# Sheet1.net
KiCad netlist of a schematic drawn in Altium Designer
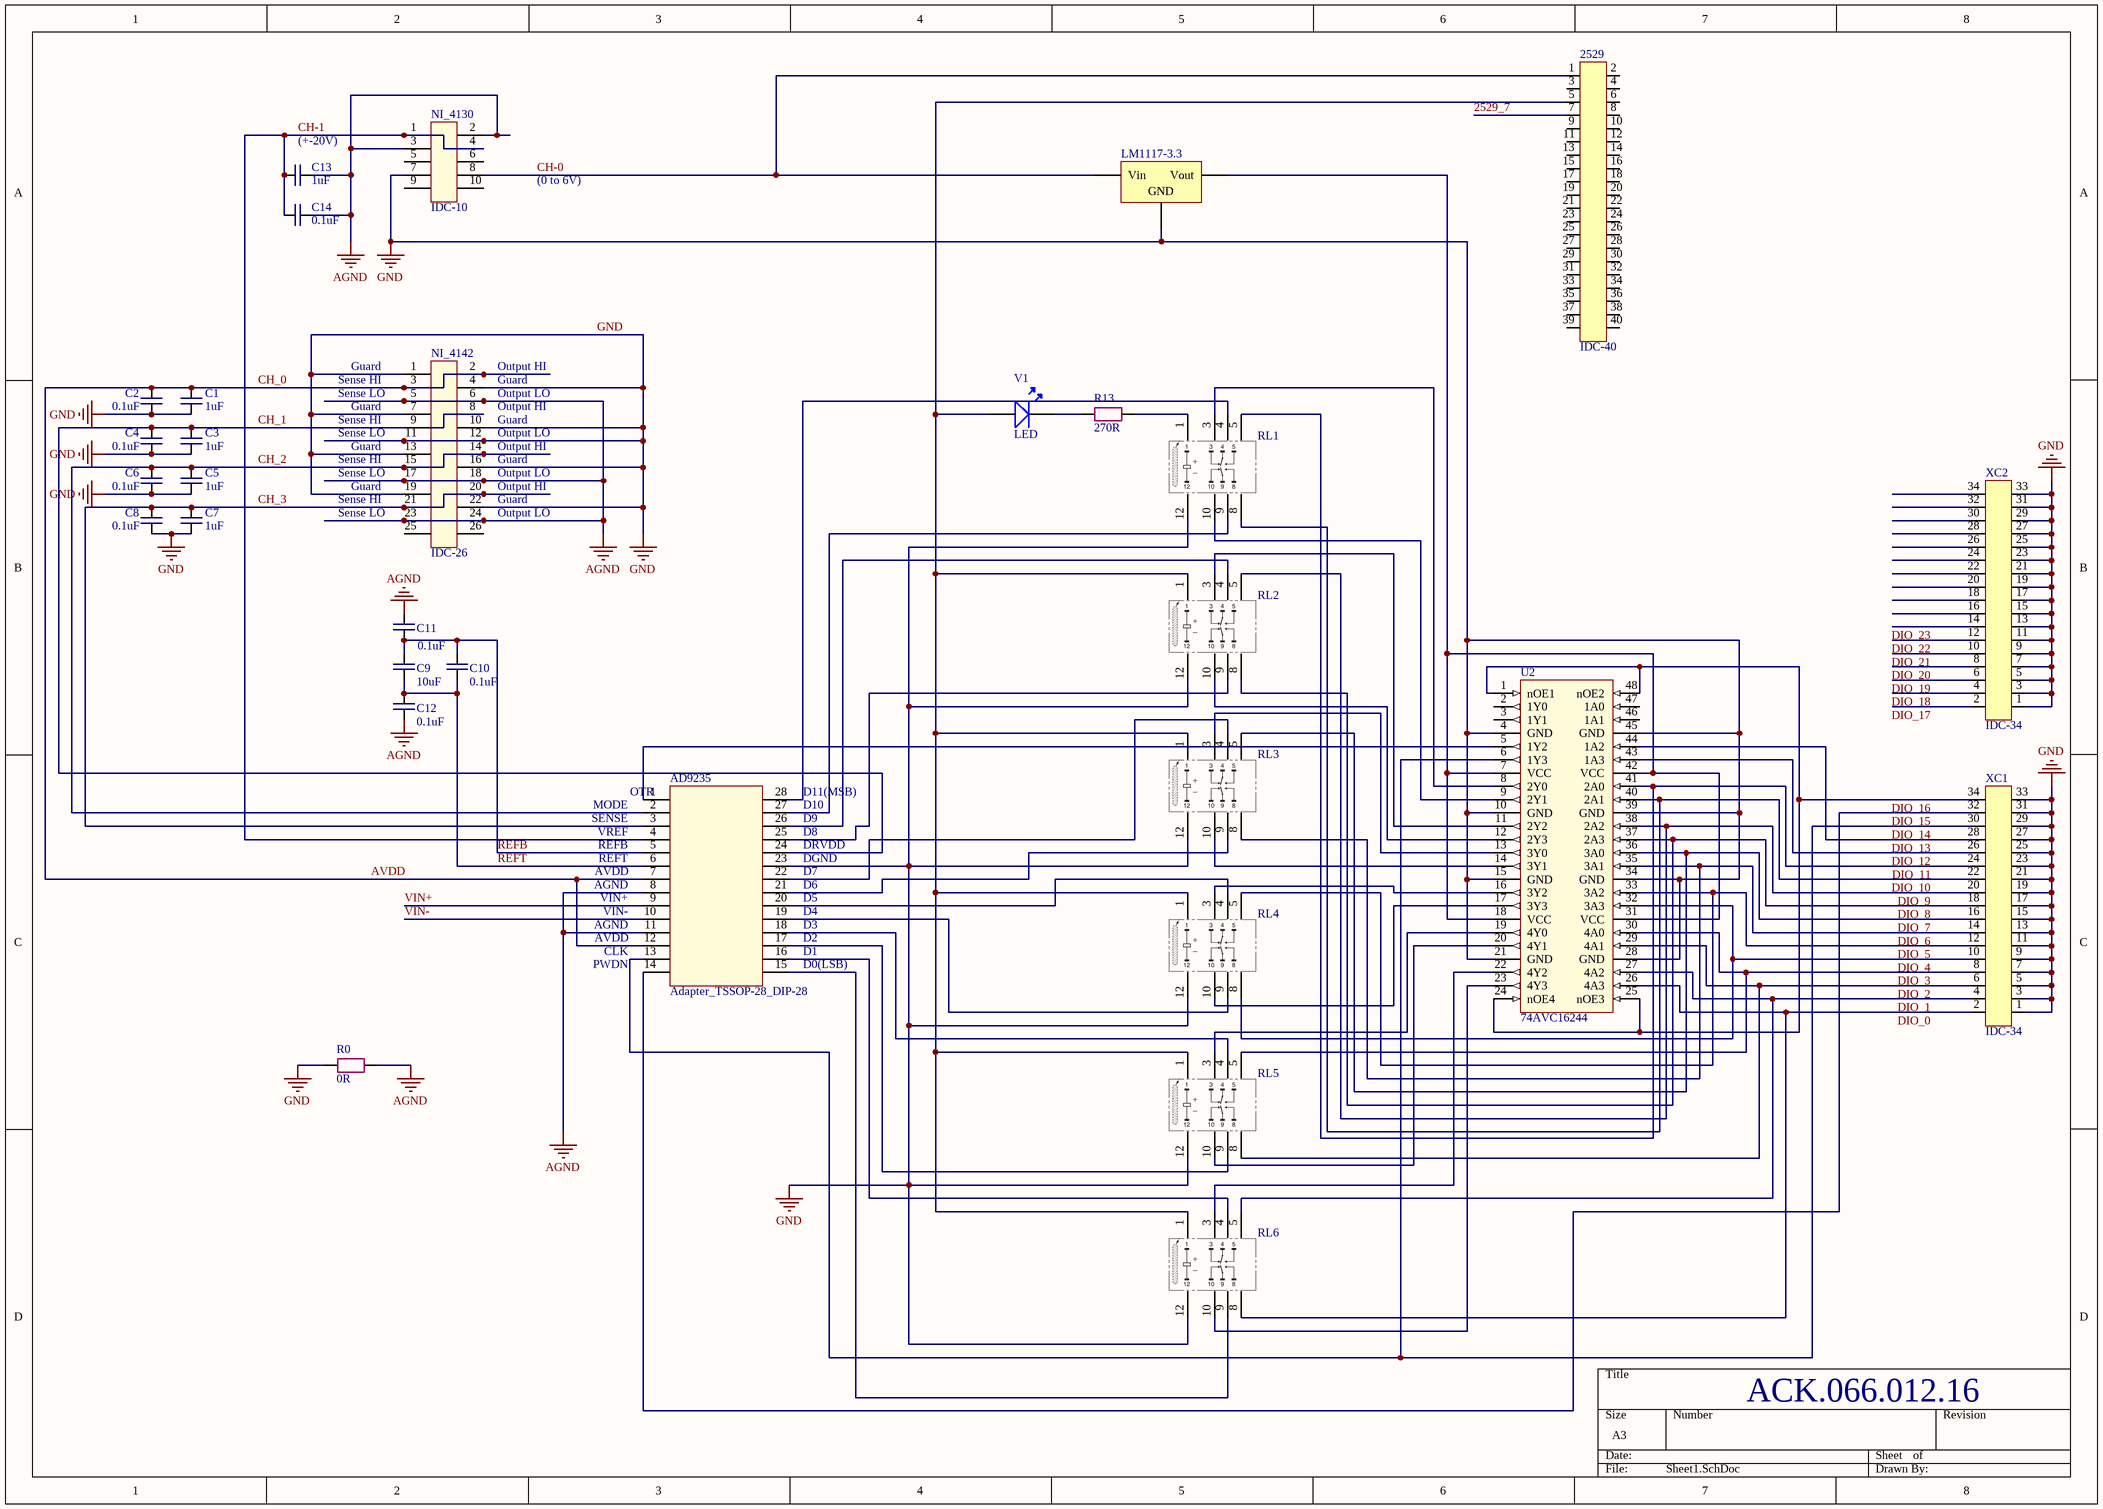
[diagram p0: Sheet1.SchDoc]

(export (version "E")
  (design (tool "Eeschema 10.0.6"))
  (components
    (comp (ref "2529")
      (value "IDC-40")
      (footprint "IDC-40")
      (description "разъем 2529")
      (libsource (lib "RCU") (part "IDC-40"))
    )
    (comp (ref "AD9235")
      (value "Adapter_TSSOP-28_DIP-28")
      (footprint "Adapter_TSSOP-28_DIP-28 - 14mm")
      (description "from aliexpress")
      (libsource (lib "RCU") (part "Adapter_TSSOP-28_DIP-28"))
    )
    (comp (ref "C1") (value "1uF") (footprint "RCU:C_0805") (libsource (lib "RCU") (part "capacitor 0805")))
    (comp (ref "C2") (value "0.1uF") (footprint "RCU:C_0805") (libsource (lib "RCU") (part "capacitor 0805")))
    (comp (ref "C3") (value "1uF") (footprint "RCU:C_0805") (libsource (lib "RCU") (part "capacitor 0805")))
    (comp (ref "C4") (value "0.1uF") (footprint "RCU:C_0805") (libsource (lib "RCU") (part "capacitor 0805")))
    (comp (ref "C5") (value "1uF") (footprint "RCU:C_0805") (libsource (lib "RCU") (part "capacitor 0805")))
    (comp (ref "C6") (value "0.1uF") (footprint "RCU:C_0805") (libsource (lib "RCU") (part "capacitor 0805")))
    (comp (ref "C7") (value "1uF") (footprint "RCU:C_0805") (libsource (lib "RCU") (part "capacitor 0805")))
    (comp (ref "C8") (value "0.1uF") (footprint "RCU:C_0805") (libsource (lib "RCU") (part "capacitor 0805")))
    (comp (ref "C9") (value "10uF") (footprint "RCU:C_0805") (libsource (lib "RCU") (part "capacitor 0805")))
    (comp (ref "C10")
      (value "0.1uF")
      (footprint "RCU:C_0805")
      (libsource (lib "RCU") (part "capacitor 0805"))
    )
    (comp (ref "C11")
      (value "0.1uF")
      (footprint "RCU:C_0805")
      (libsource (lib "RCU") (part "capacitor 0805"))
    )
    (comp (ref "C12")
      (value "0.1uF")
      (footprint "RCU:C_0805")
      (libsource (lib "RCU") (part "capacitor 0805"))
    )
    (comp (ref "C13") (value "1uF") (footprint "RCU:C_0805") (libsource (lib "RCU") (part "capacitor 0805")))
    (comp (ref "C14")
      (value "0.1uF")
      (footprint "RCU:C_0805")
      (libsource (lib "RCU") (part "capacitor 0805"))
    )
    (comp (ref "LM1117-3.3")
      (value "LM1117-3.3")
      (footprint "D2PAK_N")
      (description "Voltage Regulator")
      (fields (field (name "PUBLISHER") "Altium Limited"))
      (libsource (lib "Miscellaneous Devices") (part "Volt Reg"))
    )
    (comp (ref "NI_4130")
      (value "IDC-10")
      (footprint "IDC-10")
      (description "разъем 4130")
      (libsource (lib "RCU") (part "IDC-10"))
    )
    (comp (ref "NI_4142")
      (value "IDC-26")
      (footprint "IDC-26")
      (description "разъем 4142")
      (libsource (lib "RCU") (part "IDC-26"))
    )
    (comp (ref "R0") (value "0R") (footprint "RCU:R_0805") (libsource (lib "RCU") (part "resistor 0805")))
    (comp (ref "R13") (value "270R") (footprint "RCU:R_0805") (libsource (lib "RCU") (part "resistor 0805")))
    (comp (ref "RL1")
      (value "Relay_G6S-2")
      (footprint "Relay_G6S-2")
      (libsource (lib "RCU") (part "Relay_G6S-2"))
    )
    (comp (ref "RL2")
      (value "Relay_G6S-2")
      (footprint "Relay_G6S-2")
      (libsource (lib "RCU") (part "Relay_G6S-2"))
    )
    (comp (ref "RL3")
      (value "Relay_G6S-2")
      (footprint "Relay_G6S-2")
      (libsource (lib "RCU") (part "Relay_G6S-2"))
    )
    (comp (ref "RL4")
      (value "Relay_G6S-2")
      (footprint "Relay_G6S-2")
      (libsource (lib "RCU") (part "Relay_G6S-2"))
    )
    (comp (ref "RL5")
      (value "Relay_G6S-2")
      (footprint "Relay_G6S-2")
      (libsource (lib "RCU") (part "Relay_G6S-2"))
    )
    (comp (ref "RL6")
      (value "Relay_G6S-2")
      (footprint "Relay_G6S-2")
      (libsource (lib "RCU") (part "Relay_G6S-2"))
    )
    (comp (ref "U2")
      (value "74AVC16244")
      (footprint "74AVC16244")
      (libsource (lib "RCU") (part "74AVC16244"))
    )
    (comp (ref "V1") (value "LED") (footprint "LED") (libsource (lib "RCU") (part "LED")))
    (comp (ref "XC1") (value "IDC-34") (footprint "IDC-34") (libsource (lib "RCU") (part "IDC-34")))
    (comp (ref "XC2") (value "IDC-34") (footprint "IDC-34") (libsource (lib "RCU") (part "IDC-34")))
  )
  (nets
    (net (code "1") (name "/2529_7") (class "Default")
      (node (ref "2529") (pin "7") (pinfunction "7_7") (pintype "passive"))
    )
    (net (code "2") (name "/AVDD") (class "Default")
      (node (ref "AD9235") (pin "12") (pinfunction "11_12") (pintype "passive"))
      (node (ref "AD9235") (pin "7") (pinfunction "6_7") (pintype "passive"))
      (node (ref "C1") (pin "1") (pinfunction "1_1") (pintype "passive"))
      (node (ref "C2") (pin "1") (pinfunction "1_1") (pintype "passive"))
      (node (ref "NI_4142") (pin "2") (pinfunction "2_2") (pintype "passive"))
      (node (ref "NI_4142") (pin "3") (pinfunction "3_3") (pintype "passive"))
    )
    (net (code "3") (name "/CH-0") (class "Default")
      (node (ref "2529") (pin "1") (pinfunction "0_1") (pintype "passive"))
      (node (ref "LM1117-3.3") (pin "1") (pinfunction "Vin_1") (pintype "passive"))
      (node (ref "NI_4130") (pin "8") (pinfunction "8_8") (pintype "passive"))
    )
    (net (code "4") (name "/CH-1") (class "Default")
      (node (ref "AD9235") (pin "4") (pinfunction "3_4") (pintype "passive"))
      (node (ref "C13") (pin "1") (pinfunction "1_1") (pintype "passive"))
      (node (ref "C14") (pin "1") (pinfunction "1_1") (pintype "passive"))
      (node (ref "NI_4130") (pin "1") (pinfunction "1_1") (pintype "passive"))
      (node (ref "NI_4130") (pin "4") (pinfunction "4_4") (pintype "passive"))
    )
    (net (code "5") (name "/CH_1") (class "Default")
      (node (ref "AD9235") (pin "24") (pinfunction "23_24") (pintype "passive"))
      (node (ref "C3") (pin "1") (pinfunction "1_1") (pintype "passive"))
      (node (ref "C4") (pin "1") (pinfunction "1_1") (pintype "passive"))
      (node (ref "NI_4142") (pin "9") (pinfunction "9_9") (pintype "passive"))
    )
    (net (code "6") (name "/CH_2") (class "Default")
      (node (ref "AD9235") (pin "2") (pinfunction "1_2") (pintype "passive"))
      (node (ref "C5") (pin "1") (pinfunction "1_1") (pintype "passive"))
      (node (ref "C6") (pin "1") (pinfunction "1_1") (pintype "passive"))
      (node (ref "NI_4142") (pin "14") (pinfunction "14_14") (pintype "passive"))
      (node (ref "NI_4142") (pin "15") (pinfunction "15_15") (pintype "passive"))
    )
    (net (code "7") (name "/CH_3") (class "Default")
      (node (ref "AD9235") (pin "3") (pinfunction "2_3") (pintype "passive"))
      (node (ref "C7") (pin "1") (pinfunction "1_1") (pintype "passive"))
      (node (ref "C8") (pin "1") (pinfunction "1_1") (pintype "passive"))
      (node (ref "NI_4142") (pin "20") (pinfunction "20_20") (pintype "passive"))
      (node (ref "NI_4142") (pin "21") (pinfunction "21_21") (pintype "passive"))
    )
    (net (code "8") (name "/DIO_0") (class "Default")
      (node (ref "RL6") (pin "8") (pinfunction "8_8") (pintype "passive"))
      (node (ref "U2") (pin "26") (pinfunction "4A3_26") (pintype "input"))
      (node (ref "XC1") (pin "2") (pinfunction "2_2") (pintype "passive"))
    )
    (net (code "9") (name "/DIO_1") (class "Default")
      (node (ref "RL6") (pin "5") (pinfunction "5_5") (pintype "passive"))
      (node (ref "U2") (pin "27") (pinfunction "4A2_27") (pintype "input"))
      (node (ref "XC1") (pin "4") (pinfunction "4_4") (pintype "passive"))
    )
    (net (code "10") (name "/DIO_2") (class "Default")
      (node (ref "RL5") (pin "8") (pinfunction "8_8") (pintype "passive"))
      (node (ref "U2") (pin "29") (pinfunction "4A1_29") (pintype "input"))
      (node (ref "XC1") (pin "6") (pinfunction "6_6") (pintype "passive"))
    )
    (net (code "11") (name "/DIO_3") (class "Default")
      (node (ref "RL5") (pin "5") (pinfunction "5_5") (pintype "passive"))
      (node (ref "U2") (pin "30") (pinfunction "4A0_30") (pintype "input"))
      (node (ref "XC1") (pin "8") (pinfunction "8_8") (pintype "passive"))
    )
    (net (code "12") (name "/DIO_4") (class "Default")
      (node (ref "RL4") (pin "8") (pinfunction "8_8") (pintype "passive"))
      (node (ref "U2") (pin "32") (pinfunction "3A3_32") (pintype "input"))
      (node (ref "XC1") (pin "10") (pinfunction "10_10") (pintype "passive"))
    )
    (net (code "13") (name "/DIO_5") (class "Default")
      (node (ref "RL4") (pin "5") (pinfunction "5_5") (pintype "passive"))
      (node (ref "U2") (pin "33") (pinfunction "3A2_33") (pintype "input"))
      (node (ref "XC1") (pin "12") (pinfunction "12_12") (pintype "passive"))
    )
    (net (code "14") (name "/DIO_6") (class "Default")
      (node (ref "RL3") (pin "8") (pinfunction "8_8") (pintype "passive"))
      (node (ref "U2") (pin "35") (pinfunction "3A1_35") (pintype "input"))
      (node (ref "XC1") (pin "14") (pinfunction "14_14") (pintype "passive"))
    )
    (net (code "15") (name "/DIO_7") (class "Default")
      (node (ref "RL3") (pin "5") (pinfunction "5_5") (pintype "passive"))
      (node (ref "U2") (pin "36") (pinfunction "3A0_36") (pintype "input"))
      (node (ref "XC1") (pin "16") (pinfunction "16_16") (pintype "passive"))
    )
    (net (code "16") (name "/DIO_8") (class "Default")
      (node (ref "RL2") (pin "8") (pinfunction "8_8") (pintype "passive"))
      (node (ref "U2") (pin "37") (pinfunction "2A3_37") (pintype "input"))
      (node (ref "XC1") (pin "18") (pinfunction "18_18") (pintype "passive"))
    )
    (net (code "17") (name "/DIO_9") (class "Default")
      (node (ref "RL2") (pin "5") (pinfunction "5_5") (pintype "passive"))
      (node (ref "U2") (pin "38") (pinfunction "2A2_38") (pintype "input"))
      (node (ref "XC1") (pin "20") (pinfunction "20_20") (pintype "passive"))
    )
    (net (code "18") (name "/DIO_10") (class "Default")
      (node (ref "RL1") (pin "8") (pinfunction "8_8") (pintype "passive"))
      (node (ref "U2") (pin "40") (pinfunction "2A1_40") (pintype "input"))
      (node (ref "XC1") (pin "22") (pinfunction "22_22") (pintype "passive"))
    )
    (net (code "19") (name "/DIO_11") (class "Default")
      (node (ref "RL1") (pin "5") (pinfunction "5_5") (pintype "passive"))
      (node (ref "U2") (pin "41") (pinfunction "2A0_41") (pintype "input"))
      (node (ref "XC1") (pin "24") (pinfunction "24_24") (pintype "passive"))
    )
    (net (code "20") (name "/DIO_12") (class "Default")
      (node (ref "U2") (pin "43") (pinfunction "1A3_43") (pintype "input"))
      (node (ref "XC1") (pin "26") (pinfunction "26_26") (pintype "passive"))
    )
    (net (code "21") (name "/DIO_13") (class "Default")
      (node (ref "U2") (pin "44") (pinfunction "1A2_44") (pintype "input"))
      (node (ref "XC1") (pin "28") (pinfunction "28_28") (pintype "passive"))
    )
    (net (code "22") (name "/DIO_14") (class "Default")
      (node (ref "AD9235") (pin "13") (pinfunction "12_13") (pintype "passive"))
      (node (ref "U2") (pin "6") (pinfunction "1Y3_6") (pintype "output"))
      (node (ref "XC1") (pin "30") (pinfunction "30_30") (pintype "passive"))
    )
    (net (code "23") (name "/DIO_15") (class "Default")
      (node (ref "AD9235") (pin "14") (pinfunction "13_14") (pintype "passive"))
      (node (ref "XC1") (pin "32") (pinfunction "32_32") (pintype "passive"))
    )
    (net (code "24") (name "/DIO_16") (class "Default")
      (node (ref "U2") (pin "1") (pinfunction "nOE1_1") (pintype "input"))
      (node (ref "U2") (pin "24") (pinfunction "nOE4_24") (pintype "input"))
      (node (ref "U2") (pin "25") (pinfunction "nOE3_25") (pintype "input"))
      (node (ref "U2") (pin "48") (pinfunction "nOE2_48") (pintype "input"))
      (node (ref "XC1") (pin "34") (pinfunction "34_34") (pintype "passive"))
    )
    (net (code "25") (name "/DIO_17") (class "Default")
      (node (ref "XC2") (pin "2") (pinfunction "2_2") (pintype "passive"))
    )
    (net (code "26") (name "/DIO_18") (class "Default")
      (node (ref "XC2") (pin "4") (pinfunction "4_4") (pintype "passive"))
    )
    (net (code "27") (name "/DIO_19") (class "Default")
      (node (ref "XC2") (pin "6") (pinfunction "6_6") (pintype "passive"))
    )
    (net (code "28") (name "/DIO_20") (class "Default")
      (node (ref "XC2") (pin "8") (pinfunction "8_8") (pintype "passive"))
    )
    (net (code "29") (name "/DIO_21") (class "Default")
      (node (ref "XC2") (pin "10") (pinfunction "10_10") (pintype "passive"))
    )
    (net (code "30") (name "/DIO_22") (class "Default")
      (node (ref "XC2") (pin "12") (pinfunction "12_12") (pintype "passive"))
    )
    (net (code "31") (name "/DIO_23") (class "Default")
      (node (ref "XC2") (pin "14") (pinfunction "14_14") (pintype "passive"))
    )
    (net (code "32") (name "/REFB") (class "Default")
      (node (ref "AD9235") (pin "5") (pinfunction "4_5") (pintype "passive"))
      (node (ref "C10") (pin "2") (pinfunction "2_2") (pintype "passive"))
      (node (ref "C11") (pin "1") (pinfunction "1_1") (pintype "passive"))
      (node (ref "C9") (pin "2") (pinfunction "2_2") (pintype "passive"))
    )
    (net (code "33") (name "/REFT") (class "Default")
      (node (ref "AD9235") (pin "6") (pinfunction "5_6") (pintype "passive"))
      (node (ref "C10") (pin "1") (pinfunction "1_1") (pintype "passive"))
      (node (ref "C12") (pin "2") (pinfunction "2_2") (pintype "passive"))
      (node (ref "C9") (pin "1") (pinfunction "1_1") (pintype "passive"))
    )
    (net (code "34") (name "/VIN+") (class "Default")
      (node (ref "AD9235") (pin "9") (pinfunction "8_9") (pintype "passive"))
    )
    (net (code "35") (name "/VIN-") (class "Default")
      (node (ref "AD9235") (pin "10") (pinfunction "9_10") (pintype "passive"))
    )
    (net (code "36") (name "AGND") (class "Default")
      (node (ref "AD9235") (pin "11") (pinfunction "10_11") (pintype "passive"))
      (node (ref "AD9235") (pin "8") (pinfunction "7_8") (pintype "passive"))
      (node (ref "C11") (pin "2") (pinfunction "2_2") (pintype "passive"))
      (node (ref "C12") (pin "1") (pinfunction "1_1") (pintype "passive"))
      (node (ref "C13") (pin "2") (pinfunction "2_2") (pintype "passive"))
      (node (ref "C14") (pin "2") (pinfunction "2_2") (pintype "passive"))
      (node (ref "NI_4130") (pin "2") (pinfunction "2_2") (pintype "passive"))
      (node (ref "NI_4130") (pin "3") (pinfunction "3_3") (pintype "passive"))
      (node (ref "NI_4142") (pin "17") (pinfunction "17_17") (pintype "passive"))
      (node (ref "NI_4142") (pin "18") (pinfunction "18_18") (pintype "passive"))
      (node (ref "NI_4142") (pin "23") (pinfunction "23_23") (pintype "passive"))
      (node (ref "NI_4142") (pin "24") (pinfunction "24_24") (pintype "passive"))
      (node (ref "NI_4142") (pin "5") (pinfunction "5_5") (pintype "passive"))
      (node (ref "NI_4142") (pin "6") (pinfunction "6_6") (pintype "passive"))
      (node (ref "R0") (pin "1") (pinfunction "1_1") (pintype "passive"))
    )
    (net (code "37") (name "GND") (class "Default")
      (node (ref "AD9235") (pin "23") (pinfunction "22_23") (pintype "passive"))
      (node (ref "C1") (pin "2") (pinfunction "2_2") (pintype "passive"))
      (node (ref "C2") (pin "2") (pinfunction "2_2") (pintype "passive"))
      (node (ref "C3") (pin "2") (pinfunction "2_2") (pintype "passive"))
      (node (ref "C4") (pin "2") (pinfunction "2_2") (pintype "passive"))
      (node (ref "C5") (pin "2") (pinfunction "2_2") (pintype "passive"))
      (node (ref "C6") (pin "2") (pinfunction "2_2") (pintype "passive"))
      (node (ref "C7") (pin "2") (pinfunction "2_2") (pintype "passive"))
      (node (ref "C8") (pin "2") (pinfunction "2_2") (pintype "passive"))
      (node (ref "LM1117-3.3") (pin "2") (pinfunction "GND_2") (pintype "passive"))
      (node (ref "NI_4130") (pin "7") (pinfunction "7_7") (pintype "passive"))
      (node (ref "NI_4142") (pin "1") (pinfunction "145_1") (pintype "passive"))
      (node (ref "NI_4142") (pin "10") (pinfunction "10_10") (pintype "passive"))
      (node (ref "NI_4142") (pin "11") (pinfunction "11_11") (pintype "passive"))
      (node (ref "NI_4142") (pin "12") (pinfunction "12_12") (pintype "passive"))
      (node (ref "NI_4142") (pin "13") (pinfunction "13_13") (pintype "passive"))
      (node (ref "NI_4142") (pin "16") (pinfunction "16_16") (pintype "passive"))
      (node (ref "NI_4142") (pin "19") (pinfunction "19_19") (pintype "passive"))
      (node (ref "NI_4142") (pin "22") (pinfunction "22_22") (pintype "passive"))
      (node (ref "NI_4142") (pin "4") (pinfunction "4_4") (pintype "passive"))
      (node (ref "NI_4142") (pin "7") (pinfunction "7_7") (pintype "passive"))
      (node (ref "R0") (pin "2") (pinfunction "2_2") (pintype "passive"))
      (node (ref "RL1") (pin "12") (pinfunction "12_12") (pintype "passive"))
      (node (ref "RL2") (pin "12") (pinfunction "12_12") (pintype "passive"))
      (node (ref "RL3") (pin "12") (pinfunction "12_12") (pintype "passive"))
      (node (ref "RL4") (pin "12") (pinfunction "12_12") (pintype "passive"))
      (node (ref "RL5") (pin "12") (pinfunction "12_12") (pintype "passive"))
      (node (ref "RL6") (pin "12") (pinfunction "12_12") (pintype "passive"))
      (node (ref "U2") (pin "10") (pinfunction "GND_10") (pintype "passive"))
      (node (ref "U2") (pin "15") (pinfunction "GND_15") (pintype "passive"))
      (node (ref "U2") (pin "21") (pinfunction "GND_21") (pintype "passive"))
      (node (ref "U2") (pin "28") (pinfunction "GND_28") (pintype "passive"))
      (node (ref "U2") (pin "34") (pinfunction "GND_34") (pintype "passive"))
      (node (ref "U2") (pin "39") (pinfunction "GND_39") (pintype "passive"))
      (node (ref "U2") (pin "4") (pinfunction "GND_4") (pintype "passive"))
      (node (ref "U2") (pin "45") (pinfunction "GND_45") (pintype "passive"))
      (node (ref "XC1") (pin "1") (pinfunction "0_1") (pintype "passive"))
      (node (ref "XC1") (pin "11") (pinfunction "11_11") (pintype "passive"))
      (node (ref "XC1") (pin "13") (pinfunction "13_13") (pintype "passive"))
      (node (ref "XC1") (pin "15") (pinfunction "15_15") (pintype "passive"))
      (node (ref "XC1") (pin "17") (pinfunction "17_17") (pintype "passive"))
      (node (ref "XC1") (pin "19") (pinfunction "19_19") (pintype "passive"))
      (node (ref "XC1") (pin "21") (pinfunction "21_21") (pintype "passive"))
      (node (ref "XC1") (pin "23") (pinfunction "23_23") (pintype "passive"))
      (node (ref "XC1") (pin "25") (pinfunction "25_25") (pintype "passive"))
      (node (ref "XC1") (pin "27") (pinfunction "27_27") (pintype "passive"))
      (node (ref "XC1") (pin "29") (pinfunction "29_29") (pintype "passive"))
      (node (ref "XC1") (pin "3") (pinfunction "3_3") (pintype "passive"))
      (node (ref "XC1") (pin "31") (pinfunction "31_31") (pintype "passive"))
      (node (ref "XC1") (pin "33") (pinfunction "33_33") (pintype "passive"))
      (node (ref "XC1") (pin "5") (pinfunction "5_5") (pintype "passive"))
      (node (ref "XC1") (pin "7") (pinfunction "7_7") (pintype "passive"))
      (node (ref "XC1") (pin "9") (pinfunction "9_9") (pintype "passive"))
      (node (ref "XC2") (pin "1") (pinfunction "0_1") (pintype "passive"))
      (node (ref "XC2") (pin "11") (pinfunction "11_11") (pintype "passive"))
      (node (ref "XC2") (pin "13") (pinfunction "13_13") (pintype "passive"))
      (node (ref "XC2") (pin "15") (pinfunction "15_15") (pintype "passive"))
      (node (ref "XC2") (pin "17") (pinfunction "17_17") (pintype "passive"))
      (node (ref "XC2") (pin "19") (pinfunction "19_19") (pintype "passive"))
      (node (ref "XC2") (pin "21") (pinfunction "21_21") (pintype "passive"))
      (node (ref "XC2") (pin "23") (pinfunction "23_23") (pintype "passive"))
      (node (ref "XC2") (pin "25") (pinfunction "25_25") (pintype "passive"))
      (node (ref "XC2") (pin "27") (pinfunction "27_27") (pintype "passive"))
      (node (ref "XC2") (pin "29") (pinfunction "29_29") (pintype "passive"))
      (node (ref "XC2") (pin "3") (pinfunction "3_3") (pintype "passive"))
      (node (ref "XC2") (pin "31") (pinfunction "31_31") (pintype "passive"))
      (node (ref "XC2") (pin "33") (pinfunction "33_33") (pintype "passive"))
      (node (ref "XC2") (pin "5") (pinfunction "5_5") (pintype "passive"))
      (node (ref "XC2") (pin "7") (pinfunction "7_7") (pintype "passive"))
      (node (ref "XC2") (pin "9") (pinfunction "9_9") (pintype "passive"))
    )
    (net (code "38") (name "Net-(2529-Pad5)") (class "Default")
      (node (ref "2529") (pin "5") (pinfunction "5_5") (pintype "passive"))
      (node (ref "RL2") (pin "1") (pinfunction "1_1") (pintype "passive"))
      (node (ref "RL3") (pin "1") (pinfunction "1_1") (pintype "passive"))
      (node (ref "RL4") (pin "1") (pinfunction "1_1") (pintype "passive"))
      (node (ref "RL5") (pin "1") (pinfunction "1_1") (pintype "passive"))
      (node (ref "RL6") (pin "1") (pinfunction "1_1") (pintype "passive"))
      (node (ref "V1") (pin "1") (pinfunction "1_1") (pintype "passive"))
    )
    (net (code "39") (name "Net-(AD9235-0)") (class "Default")
      (node (ref "AD9235") (pin "1") (pinfunction "0_1") (pintype "passive"))
      (node (ref "U2") (pin "5") (pinfunction "1Y2_5") (pintype "output"))
    )
    (net (code "40") (name "Net-(AD9235-14)") (class "Default")
      (node (ref "AD9235") (pin "15") (pinfunction "14_15") (pintype "passive"))
      (node (ref "RL6") (pin "9") (pinfunction "9_9") (pintype "passive"))
    )
    (net (code "41") (name "Net-(AD9235-15)") (class "Default")
      (node (ref "AD9235") (pin "16") (pinfunction "15_16") (pintype "passive"))
      (node (ref "RL6") (pin "4") (pinfunction "4_4") (pintype "passive"))
    )
    (net (code "42") (name "Net-(AD9235-16)") (class "Default")
      (node (ref "AD9235") (pin "17") (pinfunction "16_17") (pintype "passive"))
      (node (ref "RL5") (pin "9") (pinfunction "9_9") (pintype "passive"))
    )
    (net (code "43") (name "Net-(AD9235-17)") (class "Default")
      (node (ref "AD9235") (pin "18") (pinfunction "17_18") (pintype "passive"))
      (node (ref "RL5") (pin "4") (pinfunction "4_4") (pintype "passive"))
    )
    (net (code "44") (name "Net-(AD9235-18)") (class "Default")
      (node (ref "AD9235") (pin "19") (pinfunction "18_19") (pintype "passive"))
      (node (ref "RL4") (pin "9") (pinfunction "9_9") (pintype "passive"))
    )
    (net (code "45") (name "Net-(AD9235-19)") (class "Default")
      (node (ref "AD9235") (pin "20") (pinfunction "19_20") (pintype "passive"))
      (node (ref "RL4") (pin "4") (pinfunction "4_4") (pintype "passive"))
    )
    (net (code "46") (name "Net-(AD9235-20)") (class "Default")
      (node (ref "AD9235") (pin "21") (pinfunction "20_21") (pintype "passive"))
      (node (ref "RL3") (pin "9") (pinfunction "9_9") (pintype "passive"))
    )
    (net (code "47") (name "Net-(AD9235-21)") (class "Default")
      (node (ref "AD9235") (pin "22") (pinfunction "21_22") (pintype "passive"))
      (node (ref "RL3") (pin "4") (pinfunction "4_4") (pintype "passive"))
    )
    (net (code "48") (name "Net-(AD9235-24)") (class "Default")
      (node (ref "AD9235") (pin "25") (pinfunction "24_25") (pintype "passive"))
      (node (ref "RL2") (pin "9") (pinfunction "9_9") (pintype "passive"))
    )
    (net (code "49") (name "Net-(AD9235-25)") (class "Default")
      (node (ref "AD9235") (pin "26") (pinfunction "25_26") (pintype "passive"))
      (node (ref "RL2") (pin "4") (pinfunction "4_4") (pintype "passive"))
    )
    (net (code "50") (name "Net-(AD9235-26)") (class "Default")
      (node (ref "AD9235") (pin "27") (pinfunction "26_27") (pintype "passive"))
      (node (ref "RL1") (pin "9") (pinfunction "9_9") (pintype "passive"))
    )
    (net (code "51") (name "Net-(AD9235-27)") (class "Default")
      (node (ref "AD9235") (pin "28") (pinfunction "27_28") (pintype "passive"))
      (node (ref "RL1") (pin "4") (pinfunction "4_4") (pintype "passive"))
    )
    (net (code "52") (name "Net-(LM1117-3.3-Vout)") (class "Default")
      (node (ref "LM1117-3.3") (pin "3") (pinfunction "Vout_3") (pintype "passive"))
      (node (ref "U2") (pin "18") (pinfunction "VCC_18") (pintype "power_in"))
      (node (ref "U2") (pin "31") (pinfunction "VCC_31") (pintype "power_in"))
      (node (ref "U2") (pin "42") (pinfunction "VCC_42") (pintype "power_in"))
      (node (ref "U2") (pin "7") (pinfunction "VCC_7") (pintype "power_in"))
    )
    (net (code "53") (name "Net-(R13-Pad1)") (class "Default")
      (node (ref "R13") (pin "1") (pinfunction "1_1") (pintype "passive"))
      (node (ref "RL1") (pin "1") (pinfunction "1_1") (pintype "passive"))
    )
    (net (code "54") (name "Net-(R13-Pad2)") (class "Default")
      (node (ref "R13") (pin "2") (pinfunction "2_2") (pintype "passive"))
      (node (ref "V1") (pin "2") (pinfunction "2_2") (pintype "passive"))
    )
    (net (code "55") (name "Net-(U2-2Y0)") (class "Default")
      (node (ref "RL1") (pin "3") (pinfunction "3_3") (pintype "passive"))
      (node (ref "U2") (pin "8") (pinfunction "2Y0_8") (pintype "output"))
    )
    (net (code "56") (name "Net-(U2-2Y1)") (class "Default")
      (node (ref "RL1") (pin "10") (pinfunction "10_10") (pintype "passive"))
      (node (ref "U2") (pin "9") (pinfunction "2Y1_9") (pintype "output"))
    )
    (net (code "57") (name "Net-(U2-2Y2)") (class "Default")
      (node (ref "RL2") (pin "3") (pinfunction "3_3") (pintype "passive"))
      (node (ref "U2") (pin "11") (pinfunction "2Y2_11") (pintype "output"))
    )
    (net (code "58") (name "Net-(U2-2Y3)") (class "Default")
      (node (ref "RL2") (pin "10") (pinfunction "10_10") (pintype "passive"))
      (node (ref "U2") (pin "12") (pinfunction "2Y3_12") (pintype "output"))
    )
    (net (code "59") (name "Net-(U2-3Y0)") (class "Default")
      (node (ref "RL3") (pin "3") (pinfunction "3_3") (pintype "passive"))
      (node (ref "U2") (pin "13") (pinfunction "3Y0_13") (pintype "output"))
    )
    (net (code "60") (name "Net-(U2-3Y1)") (class "Default")
      (node (ref "RL3") (pin "10") (pinfunction "10_10") (pintype "passive"))
      (node (ref "U2") (pin "14") (pinfunction "3Y1_14") (pintype "output"))
    )
    (net (code "61") (name "Net-(U2-3Y2)") (class "Default")
      (node (ref "RL4") (pin "3") (pinfunction "3_3") (pintype "passive"))
      (node (ref "U2") (pin "16") (pinfunction "3Y2_16") (pintype "output"))
    )
    (net (code "62") (name "Net-(U2-3Y3)") (class "Default")
      (node (ref "RL4") (pin "10") (pinfunction "10_10") (pintype "passive"))
      (node (ref "U2") (pin "17") (pinfunction "3Y3_17") (pintype "output"))
    )
    (net (code "63") (name "Net-(U2-4Y0)") (class "Default")
      (node (ref "RL5") (pin "3") (pinfunction "3_3") (pintype "passive"))
      (node (ref "U2") (pin "19") (pinfunction "4Y0_19") (pintype "output"))
    )
    (net (code "64") (name "Net-(U2-4Y1)") (class "Default")
      (node (ref "RL5") (pin "10") (pinfunction "10_10") (pintype "passive"))
      (node (ref "U2") (pin "20") (pinfunction "4Y1_20") (pintype "output"))
    )
    (net (code "65") (name "Net-(U2-4Y2)") (class "Default")
      (node (ref "RL6") (pin "3") (pinfunction "3_3") (pintype "passive"))
      (node (ref "U2") (pin "22") (pinfunction "4Y2_22") (pintype "output"))
    )
    (net (code "66") (name "Net-(U2-4Y3)") (class "Default")
      (node (ref "RL6") (pin "10") (pinfunction "10_10") (pintype "passive"))
      (node (ref "U2") (pin "23") (pinfunction "4Y3_23") (pintype "output"))
    )
    (net (code "67") (name "unconnected-(2529-Pad2)") (class "Default")
      (node (ref "2529") (pin "2") (pinfunction "2_2") (pintype "passive"))
    )
    (net (code "68") (name "unconnected-(2529-Pad3)") (class "Default")
      (node (ref "2529") (pin "3") (pinfunction "3_3") (pintype "passive"))
    )
    (net (code "69") (name "unconnected-(2529-Pad4)") (class "Default")
      (node (ref "2529") (pin "4") (pinfunction "4_4") (pintype "passive"))
    )
    (net (code "70") (name "unconnected-(2529-Pad6)") (class "Default")
      (node (ref "2529") (pin "6") (pinfunction "6_6") (pintype "passive"))
    )
    (net (code "71") (name "unconnected-(2529-Pad8)") (class "Default")
      (node (ref "2529") (pin "8") (pinfunction "8_8") (pintype "passive"))
    )
    (net (code "72") (name "unconnected-(2529-Pad9)") (class "Default")
      (node (ref "2529") (pin "9") (pinfunction "9_9") (pintype "passive"))
    )
    (net (code "73") (name "unconnected-(2529-Pad10)") (class "Default")
      (node (ref "2529") (pin "10") (pinfunction "10_10") (pintype "passive"))
    )
    (net (code "74") (name "unconnected-(2529-Pad11)") (class "Default")
      (node (ref "2529") (pin "11") (pinfunction "11_11") (pintype "passive"))
    )
    (net (code "75") (name "unconnected-(2529-Pad12)") (class "Default")
      (node (ref "2529") (pin "12") (pinfunction "12_12") (pintype "passive"))
    )
    (net (code "76") (name "unconnected-(2529-Pad13)") (class "Default")
      (node (ref "2529") (pin "13") (pinfunction "13_13") (pintype "passive"))
    )
    (net (code "77") (name "unconnected-(2529-Pad14)") (class "Default")
      (node (ref "2529") (pin "14") (pinfunction "14_14") (pintype "passive"))
    )
    (net (code "78") (name "unconnected-(2529-Pad15)") (class "Default")
      (node (ref "2529") (pin "15") (pinfunction "15_15") (pintype "passive"))
    )
    (net (code "79") (name "unconnected-(2529-Pad16)") (class "Default")
      (node (ref "2529") (pin "16") (pinfunction "16_16") (pintype "passive"))
    )
    (net (code "80") (name "unconnected-(2529-Pad17)") (class "Default")
      (node (ref "2529") (pin "17") (pinfunction "17_17") (pintype "passive"))
    )
    (net (code "81") (name "unconnected-(2529-Pad18)") (class "Default")
      (node (ref "2529") (pin "18") (pinfunction "18_18") (pintype "passive"))
    )
    (net (code "82") (name "unconnected-(2529-Pad19)") (class "Default")
      (node (ref "2529") (pin "19") (pinfunction "19_19") (pintype "passive"))
    )
    (net (code "83") (name "unconnected-(2529-Pad20)") (class "Default")
      (node (ref "2529") (pin "20") (pinfunction "20_20") (pintype "passive"))
    )
    (net (code "84") (name "unconnected-(2529-Pad21)") (class "Default")
      (node (ref "2529") (pin "21") (pinfunction "21_21") (pintype "passive"))
    )
    (net (code "85") (name "unconnected-(2529-Pad22)") (class "Default")
      (node (ref "2529") (pin "22") (pinfunction "22_22") (pintype "passive"))
    )
    (net (code "86") (name "unconnected-(2529-Pad23)") (class "Default")
      (node (ref "2529") (pin "23") (pinfunction "23_23") (pintype "passive"))
    )
    (net (code "87") (name "unconnected-(2529-Pad24)") (class "Default")
      (node (ref "2529") (pin "24") (pinfunction "24_24") (pintype "passive"))
    )
    (net (code "88") (name "unconnected-(2529-Pad25)") (class "Default")
      (node (ref "2529") (pin "25") (pinfunction "25_25") (pintype "passive"))
    )
    (net (code "89") (name "unconnected-(2529-Pad26)") (class "Default")
      (node (ref "2529") (pin "26") (pinfunction "26_26") (pintype "passive"))
    )
    (net (code "90") (name "unconnected-(2529-Pad27)") (class "Default")
      (node (ref "2529") (pin "27") (pinfunction "27_27") (pintype "passive"))
    )
    (net (code "91") (name "unconnected-(2529-Pad28)") (class "Default")
      (node (ref "2529") (pin "28") (pinfunction "28_28") (pintype "passive"))
    )
    (net (code "92") (name "unconnected-(2529-Pad29)") (class "Default")
      (node (ref "2529") (pin "29") (pinfunction "29_29") (pintype "passive"))
    )
    (net (code "93") (name "unconnected-(2529-Pad30)") (class "Default")
      (node (ref "2529") (pin "30") (pinfunction "30_30") (pintype "passive"))
    )
    (net (code "94") (name "unconnected-(2529-Pad31)") (class "Default")
      (node (ref "2529") (pin "31") (pinfunction "31_31") (pintype "passive"))
    )
    (net (code "95") (name "unconnected-(2529-Pad32)") (class "Default")
      (node (ref "2529") (pin "32") (pinfunction "32_32") (pintype "passive"))
    )
    (net (code "96") (name "unconnected-(2529-Pad33)") (class "Default")
      (node (ref "2529") (pin "33") (pinfunction "33_33") (pintype "passive"))
    )
    (net (code "97") (name "unconnected-(2529-Pad34)") (class "Default")
      (node (ref "2529") (pin "34") (pinfunction "34_34") (pintype "passive"))
    )
    (net (code "98") (name "unconnected-(2529-Pad35)") (class "Default")
      (node (ref "2529") (pin "35") (pinfunction "35_35") (pintype "passive"))
    )
    (net (code "99") (name "unconnected-(2529-Pad36)") (class "Default")
      (node (ref "2529") (pin "36") (pinfunction "36_36") (pintype "passive"))
    )
    (net (code "100") (name "unconnected-(2529-Pad37)") (class "Default")
      (node (ref "2529") (pin "37") (pinfunction "37_37") (pintype "passive"))
    )
    (net (code "101") (name "unconnected-(2529-Pad38)") (class "Default")
      (node (ref "2529") (pin "38") (pinfunction "38_38") (pintype "passive"))
    )
    (net (code "102") (name "unconnected-(2529-Pad39)") (class "Default")
      (node (ref "2529") (pin "39") (pinfunction "39_39") (pintype "passive"))
    )
    (net (code "103") (name "unconnected-(2529-Pad40)") (class "Default")
      (node (ref "2529") (pin "40") (pinfunction "40_40") (pintype "passive"))
    )
    (net (code "104") (name "unconnected-(NI_4130-Pad5)") (class "Default")
      (node (ref "NI_4130") (pin "5") (pinfunction "5_5") (pintype "passive"))
    )
    (net (code "105") (name "unconnected-(NI_4130-Pad6)") (class "Default")
      (node (ref "NI_4130") (pin "6") (pinfunction "6_6") (pintype "passive"))
    )
    (net (code "106") (name "unconnected-(NI_4130-Pad9)") (class "Default")
      (node (ref "NI_4130") (pin "9") (pinfunction "9_9") (pintype "passive"))
    )
    (net (code "107") (name "unconnected-(NI_4130-Pad10)") (class "Default")
      (node (ref "NI_4130") (pin "10") (pinfunction "10_10") (pintype "passive"))
    )
    (net (code "108") (name "unconnected-(NI_4142-Pad8)") (class "Default")
      (node (ref "NI_4142") (pin "8") (pinfunction "8_8") (pintype "passive"))
    )
    (net (code "109") (name "unconnected-(NI_4142-Pad25)") (class "Default")
      (node (ref "NI_4142") (pin "25") (pinfunction "25_25") (pintype "passive"))
    )
    (net (code "110") (name "unconnected-(NI_4142-Pad26)") (class "Default")
      (node (ref "NI_4142") (pin "26") (pinfunction "26_26") (pintype "passive"))
    )
    (net (code "111") (name "unconnected-(U2-1A0-Pad47)") (class "Default")
      (node (ref "U2") (pin "47") (pinfunction "1A0_47") (pintype "input"))
    )
    (net (code "112") (name "unconnected-(U2-1A1-Pad46)") (class "Default")
      (node (ref "U2") (pin "46") (pinfunction "1A1_46") (pintype "input"))
    )
    (net (code "113") (name "unconnected-(U2-1Y0-Pad2)") (class "Default")
      (node (ref "U2") (pin "2") (pinfunction "1Y0_2") (pintype "output"))
    )
    (net (code "114") (name "unconnected-(U2-1Y1-Pad3)") (class "Default")
      (node (ref "U2") (pin "3") (pinfunction "1Y1_3") (pintype "output"))
    )
    (net (code "115") (name "unconnected-(XC2-Pad16)") (class "Default")
      (node (ref "XC2") (pin "16") (pinfunction "16_16") (pintype "passive"))
    )
    (net (code "116") (name "unconnected-(XC2-Pad18)") (class "Default")
      (node (ref "XC2") (pin "18") (pinfunction "18_18") (pintype "passive"))
    )
    (net (code "117") (name "unconnected-(XC2-Pad20)") (class "Default")
      (node (ref "XC2") (pin "20") (pinfunction "20_20") (pintype "passive"))
    )
    (net (code "118") (name "unconnected-(XC2-Pad22)") (class "Default")
      (node (ref "XC2") (pin "22") (pinfunction "22_22") (pintype "passive"))
    )
    (net (code "119") (name "unconnected-(XC2-Pad24)") (class "Default")
      (node (ref "XC2") (pin "24") (pinfunction "24_24") (pintype "passive"))
    )
    (net (code "120") (name "unconnected-(XC2-Pad26)") (class "Default")
      (node (ref "XC2") (pin "26") (pinfunction "26_26") (pintype "passive"))
    )
    (net (code "121") (name "unconnected-(XC2-Pad28)") (class "Default")
      (node (ref "XC2") (pin "28") (pinfunction "28_28") (pintype "passive"))
    )
    (net (code "122") (name "unconnected-(XC2-Pad30)") (class "Default")
      (node (ref "XC2") (pin "30") (pinfunction "30_30") (pintype "passive"))
    )
    (net (code "123") (name "unconnected-(XC2-Pad32)") (class "Default")
      (node (ref "XC2") (pin "32") (pinfunction "32_32") (pintype "passive"))
    )
    (net (code "124") (name "unconnected-(XC2-Pad34)") (class "Default")
      (node (ref "XC2") (pin "34") (pinfunction "34_34") (pintype "passive"))
    )
  )
)
